# interconnect-board.net
KiCad netlist of a schematic drawn in EAGLE
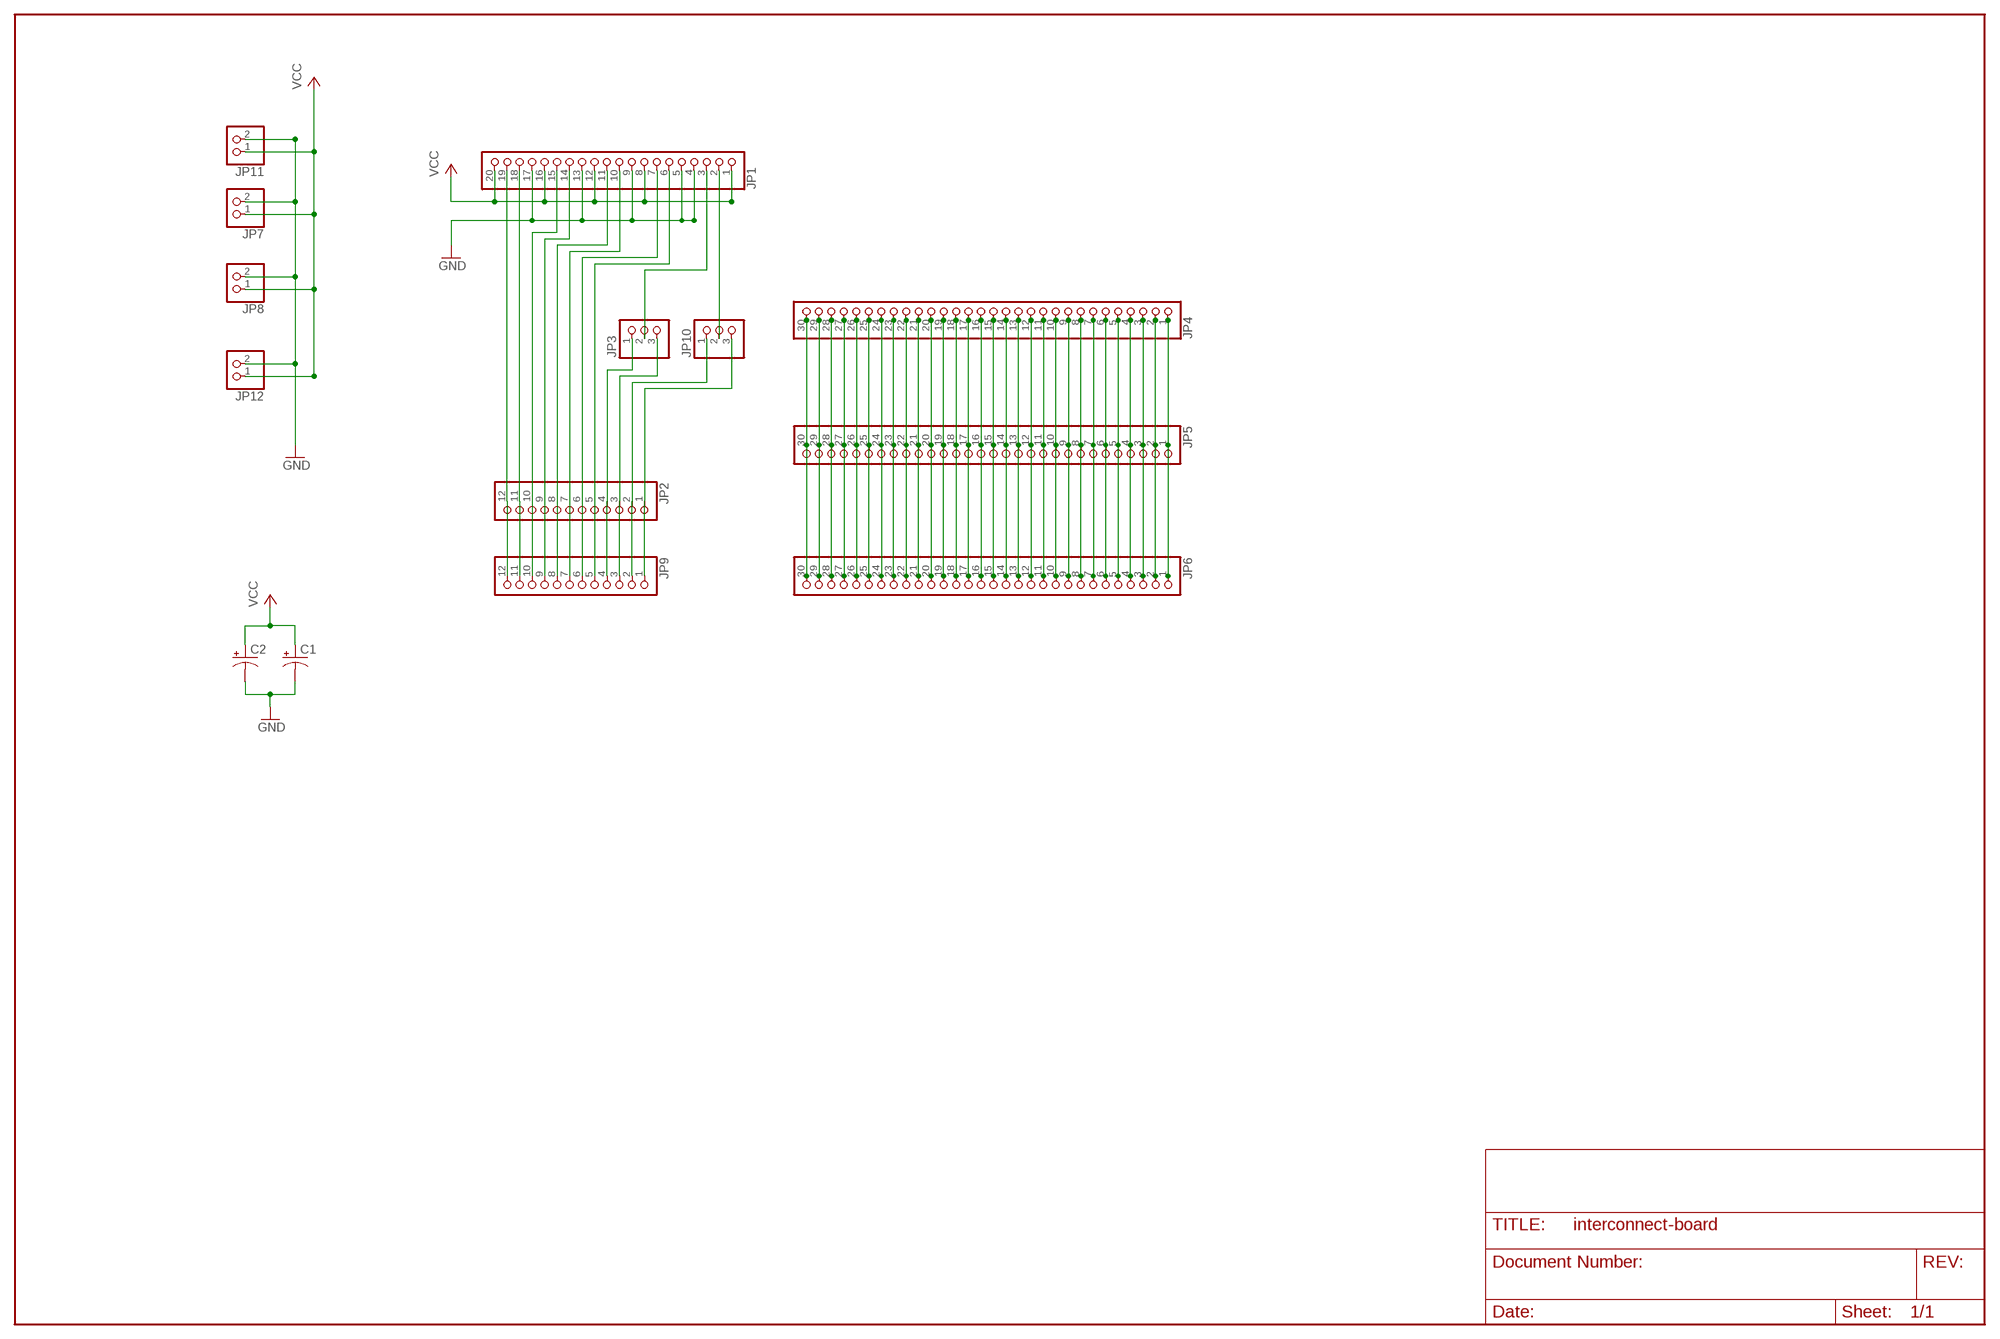
[diagram p0: schematic, sheet 1]

(export (version "E")
  (design (tool "Eeschema 10.0.6"))
  (components
    (comp (ref "C1")
      (value "CPOL-USE15-6AXIAL")
      (footprint "eagle-import:E15-6")
      (libsource (lib "eagle-import") (part "CPOL-USE15-6AXIAL"))
    )
    (comp (ref "C2")
      (value "CPOL-USE15-6AXIAL")
      (footprint "eagle-import:E15-6")
      (libsource (lib "eagle-import") (part "CPOL-USE15-6AXIAL"))
    )
    (comp (ref "JP1")
      (value "PINHD-1X20")
      (footprint "eagle-import:1X20")
      (libsource (lib "eagle-import") (part "PINHD-1X20"))
    )
    (comp (ref "JP2")
      (value "PINHD-1X12")
      (footprint "eagle-import:1X12")
      (libsource (lib "eagle-import") (part "PINHD-1X12"))
    )
    (comp (ref "JP3")
      (value "PINHD-1X3")
      (footprint "eagle-import:1X03")
      (libsource (lib "eagle-import") (part "PINHD-1X3"))
    )
    (comp (ref "JP4")
      (value "PINHD-1X30")
      (footprint "eagle-import:1X30")
      (libsource (lib "eagle-import") (part "PINHD-1X30"))
    )
    (comp (ref "JP5")
      (value "PINHD-1X30")
      (footprint "eagle-import:1X30")
      (libsource (lib "eagle-import") (part "PINHD-1X30"))
    )
    (comp (ref "JP6")
      (value "PINHD-1X30")
      (footprint "eagle-import:1X30")
      (libsource (lib "eagle-import") (part "PINHD-1X30"))
    )
    (comp (ref "JP7")
      (value "PINHD-1X2")
      (footprint "eagle-import:1X02")
      (libsource (lib "eagle-import") (part "PINHD-1X2"))
    )
    (comp (ref "JP8")
      (value "PINHD-1X2")
      (footprint "eagle-import:1X02")
      (libsource (lib "eagle-import") (part "PINHD-1X2"))
    )
    (comp (ref "JP9")
      (value "PINHD-1X12")
      (footprint "eagle-import:1X12")
      (libsource (lib "eagle-import") (part "PINHD-1X12"))
    )
    (comp (ref "JP10")
      (value "PINHD-1X3")
      (footprint "eagle-import:1X03")
      (libsource (lib "eagle-import") (part "PINHD-1X3"))
    )
    (comp (ref "JP11")
      (value "PINHD-1X2")
      (footprint "eagle-import:1X02")
      (libsource (lib "eagle-import") (part "PINHD-1X2"))
    )
    (comp (ref "JP12")
      (value "PINHD-1X2")
      (footprint "eagle-import:1X02")
      (libsource (lib "eagle-import") (part "PINHD-1X2"))
    )
  )
  (nets
    (net (code "1") (name "GND") (class "Default")
      (node (ref "C1") (pin "-") (pinfunction "-_-") (pintype "passive"))
      (node (ref "C2") (pin "-") (pinfunction "-_-") (pintype "passive"))
      (node (ref "JP1") (pin "13") (pinfunction "13_13") (pintype "passive"))
      (node (ref "JP1") (pin "17") (pinfunction "17_17") (pintype "passive"))
      (node (ref "JP1") (pin "4") (pinfunction "4_4") (pintype "passive"))
      (node (ref "JP1") (pin "5") (pinfunction "5_5") (pintype "passive"))
      (node (ref "JP1") (pin "9") (pinfunction "9_9") (pintype "passive"))
      (node (ref "JP11") (pin "2") (pinfunction "2_2") (pintype "passive"))
      (node (ref "JP12") (pin "2") (pinfunction "2_2") (pintype "passive"))
      (node (ref "JP7") (pin "2") (pinfunction "2_2") (pintype "passive"))
      (node (ref "JP8") (pin "2") (pinfunction "2_2") (pintype "passive"))
    )
    (net (code "2") (name "Net-(JP1-Pad2)") (class "Default")
      (node (ref "JP1") (pin "2") (pinfunction "2_2") (pintype "passive"))
      (node (ref "JP10") (pin "2") (pinfunction "2_2") (pintype "passive"))
    )
    (net (code "3") (name "Net-(JP1-Pad3)") (class "Default")
      (node (ref "JP1") (pin "3") (pinfunction "3_3") (pintype "passive"))
      (node (ref "JP3") (pin "2") (pinfunction "2_2") (pintype "passive"))
    )
    (net (code "4") (name "Net-(JP1-Pad6)") (class "Default")
      (node (ref "JP1") (pin "6") (pinfunction "6_6") (pintype "passive"))
      (node (ref "JP2") (pin "5") (pinfunction "5_5") (pintype "passive"))
      (node (ref "JP9") (pin "5") (pinfunction "5_5") (pintype "passive"))
    )
    (net (code "5") (name "Net-(JP1-Pad7)") (class "Default")
      (node (ref "JP1") (pin "7") (pinfunction "7_7") (pintype "passive"))
      (node (ref "JP2") (pin "6") (pinfunction "6_6") (pintype "passive"))
      (node (ref "JP9") (pin "6") (pinfunction "6_6") (pintype "passive"))
    )
    (net (code "6") (name "Net-(JP1-Pad10)") (class "Default")
      (node (ref "JP1") (pin "10") (pinfunction "10_10") (pintype "passive"))
      (node (ref "JP2") (pin "7") (pinfunction "7_7") (pintype "passive"))
      (node (ref "JP9") (pin "7") (pinfunction "7_7") (pintype "passive"))
    )
    (net (code "7") (name "Net-(JP1-Pad11)") (class "Default")
      (node (ref "JP1") (pin "11") (pinfunction "11_11") (pintype "passive"))
      (node (ref "JP2") (pin "8") (pinfunction "8_8") (pintype "passive"))
      (node (ref "JP9") (pin "8") (pinfunction "8_8") (pintype "passive"))
    )
    (net (code "8") (name "Net-(JP1-Pad14)") (class "Default")
      (node (ref "JP1") (pin "14") (pinfunction "14_14") (pintype "passive"))
      (node (ref "JP2") (pin "9") (pinfunction "9_9") (pintype "passive"))
      (node (ref "JP9") (pin "9") (pinfunction "9_9") (pintype "passive"))
    )
    (net (code "9") (name "Net-(JP1-Pad15)") (class "Default")
      (node (ref "JP1") (pin "15") (pinfunction "15_15") (pintype "passive"))
      (node (ref "JP2") (pin "10") (pinfunction "10_10") (pintype "passive"))
      (node (ref "JP9") (pin "10") (pinfunction "10_10") (pintype "passive"))
    )
    (net (code "10") (name "Net-(JP1-Pad18)") (class "Default")
      (node (ref "JP1") (pin "18") (pinfunction "18_18") (pintype "passive"))
      (node (ref "JP2") (pin "11") (pinfunction "11_11") (pintype "passive"))
      (node (ref "JP9") (pin "11") (pinfunction "11_11") (pintype "passive"))
    )
    (net (code "11") (name "Net-(JP1-Pad19)") (class "Default")
      (node (ref "JP1") (pin "19") (pinfunction "19_19") (pintype "passive"))
      (node (ref "JP2") (pin "12") (pinfunction "12_12") (pintype "passive"))
      (node (ref "JP9") (pin "12") (pinfunction "12_12") (pintype "passive"))
    )
    (net (code "12") (name "Net-(JP2-Pad3)") (class "Default")
      (node (ref "JP2") (pin "3") (pinfunction "3_3") (pintype "passive"))
      (node (ref "JP3") (pin "3") (pinfunction "3_3") (pintype "passive"))
      (node (ref "JP9") (pin "3") (pinfunction "3_3") (pintype "passive"))
    )
    (net (code "13") (name "Net-(JP2-Pad4)") (class "Default")
      (node (ref "JP2") (pin "4") (pinfunction "4_4") (pintype "passive"))
      (node (ref "JP3") (pin "1") (pinfunction "1_1") (pintype "passive"))
      (node (ref "JP9") (pin "4") (pinfunction "4_4") (pintype "passive"))
    )
    (net (code "14") (name "Net-(JP4-Pad1)") (class "Default")
      (node (ref "JP4") (pin "1") (pinfunction "1_1") (pintype "passive"))
      (node (ref "JP5") (pin "1") (pinfunction "1_1") (pintype "passive"))
      (node (ref "JP6") (pin "1") (pinfunction "1_1") (pintype "passive"))
    )
    (net (code "15") (name "Net-(JP4-Pad2)") (class "Default")
      (node (ref "JP4") (pin "2") (pinfunction "2_2") (pintype "passive"))
      (node (ref "JP5") (pin "2") (pinfunction "2_2") (pintype "passive"))
      (node (ref "JP6") (pin "2") (pinfunction "2_2") (pintype "passive"))
    )
    (net (code "16") (name "Net-(JP4-Pad3)") (class "Default")
      (node (ref "JP4") (pin "3") (pinfunction "3_3") (pintype "passive"))
      (node (ref "JP5") (pin "3") (pinfunction "3_3") (pintype "passive"))
      (node (ref "JP6") (pin "3") (pinfunction "3_3") (pintype "passive"))
    )
    (net (code "17") (name "Net-(JP4-Pad4)") (class "Default")
      (node (ref "JP4") (pin "4") (pinfunction "4_4") (pintype "passive"))
      (node (ref "JP5") (pin "4") (pinfunction "4_4") (pintype "passive"))
      (node (ref "JP6") (pin "4") (pinfunction "4_4") (pintype "passive"))
    )
    (net (code "18") (name "Net-(JP4-Pad5)") (class "Default")
      (node (ref "JP4") (pin "5") (pinfunction "5_5") (pintype "passive"))
      (node (ref "JP5") (pin "5") (pinfunction "5_5") (pintype "passive"))
      (node (ref "JP6") (pin "5") (pinfunction "5_5") (pintype "passive"))
    )
    (net (code "19") (name "Net-(JP4-Pad6)") (class "Default")
      (node (ref "JP4") (pin "6") (pinfunction "6_6") (pintype "passive"))
      (node (ref "JP5") (pin "6") (pinfunction "6_6") (pintype "passive"))
      (node (ref "JP6") (pin "6") (pinfunction "6_6") (pintype "passive"))
    )
    (net (code "20") (name "Net-(JP4-Pad7)") (class "Default")
      (node (ref "JP4") (pin "7") (pinfunction "7_7") (pintype "passive"))
      (node (ref "JP5") (pin "7") (pinfunction "7_7") (pintype "passive"))
      (node (ref "JP6") (pin "7") (pinfunction "7_7") (pintype "passive"))
    )
    (net (code "21") (name "Net-(JP4-Pad8)") (class "Default")
      (node (ref "JP4") (pin "8") (pinfunction "8_8") (pintype "passive"))
      (node (ref "JP5") (pin "8") (pinfunction "8_8") (pintype "passive"))
      (node (ref "JP6") (pin "8") (pinfunction "8_8") (pintype "passive"))
    )
    (net (code "22") (name "Net-(JP4-Pad9)") (class "Default")
      (node (ref "JP4") (pin "9") (pinfunction "9_9") (pintype "passive"))
      (node (ref "JP5") (pin "9") (pinfunction "9_9") (pintype "passive"))
      (node (ref "JP6") (pin "9") (pinfunction "9_9") (pintype "passive"))
    )
    (net (code "23") (name "Net-(JP4-Pad10)") (class "Default")
      (node (ref "JP4") (pin "10") (pinfunction "10_10") (pintype "passive"))
      (node (ref "JP5") (pin "10") (pinfunction "10_10") (pintype "passive"))
      (node (ref "JP6") (pin "10") (pinfunction "10_10") (pintype "passive"))
    )
    (net (code "24") (name "Net-(JP4-Pad11)") (class "Default")
      (node (ref "JP4") (pin "11") (pinfunction "11_11") (pintype "passive"))
      (node (ref "JP5") (pin "11") (pinfunction "11_11") (pintype "passive"))
      (node (ref "JP6") (pin "11") (pinfunction "11_11") (pintype "passive"))
    )
    (net (code "25") (name "Net-(JP4-Pad12)") (class "Default")
      (node (ref "JP4") (pin "12") (pinfunction "12_12") (pintype "passive"))
      (node (ref "JP5") (pin "12") (pinfunction "12_12") (pintype "passive"))
      (node (ref "JP6") (pin "12") (pinfunction "12_12") (pintype "passive"))
    )
    (net (code "26") (name "Net-(JP4-Pad13)") (class "Default")
      (node (ref "JP4") (pin "13") (pinfunction "13_13") (pintype "passive"))
      (node (ref "JP5") (pin "13") (pinfunction "13_13") (pintype "passive"))
      (node (ref "JP6") (pin "13") (pinfunction "13_13") (pintype "passive"))
    )
    (net (code "27") (name "Net-(JP4-Pad14)") (class "Default")
      (node (ref "JP4") (pin "14") (pinfunction "14_14") (pintype "passive"))
      (node (ref "JP5") (pin "14") (pinfunction "14_14") (pintype "passive"))
      (node (ref "JP6") (pin "14") (pinfunction "14_14") (pintype "passive"))
    )
    (net (code "28") (name "Net-(JP4-Pad15)") (class "Default")
      (node (ref "JP4") (pin "15") (pinfunction "15_15") (pintype "passive"))
      (node (ref "JP5") (pin "15") (pinfunction "15_15") (pintype "passive"))
      (node (ref "JP6") (pin "15") (pinfunction "15_15") (pintype "passive"))
    )
    (net (code "29") (name "Net-(JP4-Pad16)") (class "Default")
      (node (ref "JP4") (pin "16") (pinfunction "16_16") (pintype "passive"))
      (node (ref "JP5") (pin "16") (pinfunction "16_16") (pintype "passive"))
      (node (ref "JP6") (pin "16") (pinfunction "16_16") (pintype "passive"))
    )
    (net (code "30") (name "Net-(JP4-Pad17)") (class "Default")
      (node (ref "JP4") (pin "17") (pinfunction "17_17") (pintype "passive"))
      (node (ref "JP5") (pin "17") (pinfunction "17_17") (pintype "passive"))
      (node (ref "JP6") (pin "17") (pinfunction "17_17") (pintype "passive"))
    )
    (net (code "31") (name "Net-(JP4-Pad18)") (class "Default")
      (node (ref "JP4") (pin "18") (pinfunction "18_18") (pintype "passive"))
      (node (ref "JP5") (pin "18") (pinfunction "18_18") (pintype "passive"))
      (node (ref "JP6") (pin "18") (pinfunction "18_18") (pintype "passive"))
    )
    (net (code "32") (name "Net-(JP4-Pad19)") (class "Default")
      (node (ref "JP4") (pin "19") (pinfunction "19_19") (pintype "passive"))
      (node (ref "JP5") (pin "19") (pinfunction "19_19") (pintype "passive"))
      (node (ref "JP6") (pin "19") (pinfunction "19_19") (pintype "passive"))
    )
    (net (code "33") (name "Net-(JP4-Pad20)") (class "Default")
      (node (ref "JP4") (pin "20") (pinfunction "20_20") (pintype "passive"))
      (node (ref "JP5") (pin "20") (pinfunction "20_20") (pintype "passive"))
      (node (ref "JP6") (pin "20") (pinfunction "20_20") (pintype "passive"))
    )
    (net (code "34") (name "Net-(JP4-Pad21)") (class "Default")
      (node (ref "JP4") (pin "21") (pinfunction "21_21") (pintype "passive"))
      (node (ref "JP5") (pin "21") (pinfunction "21_21") (pintype "passive"))
      (node (ref "JP6") (pin "21") (pinfunction "21_21") (pintype "passive"))
    )
    (net (code "35") (name "Net-(JP4-Pad22)") (class "Default")
      (node (ref "JP4") (pin "22") (pinfunction "22_22") (pintype "passive"))
      (node (ref "JP5") (pin "22") (pinfunction "22_22") (pintype "passive"))
      (node (ref "JP6") (pin "22") (pinfunction "22_22") (pintype "passive"))
    )
    (net (code "36") (name "Net-(JP4-Pad23)") (class "Default")
      (node (ref "JP4") (pin "23") (pinfunction "23_23") (pintype "passive"))
      (node (ref "JP5") (pin "23") (pinfunction "23_23") (pintype "passive"))
      (node (ref "JP6") (pin "23") (pinfunction "23_23") (pintype "passive"))
    )
    (net (code "37") (name "Net-(JP4-Pad24)") (class "Default")
      (node (ref "JP4") (pin "24") (pinfunction "24_24") (pintype "passive"))
      (node (ref "JP5") (pin "24") (pinfunction "24_24") (pintype "passive"))
      (node (ref "JP6") (pin "24") (pinfunction "24_24") (pintype "passive"))
    )
    (net (code "38") (name "Net-(JP4-Pad25)") (class "Default")
      (node (ref "JP4") (pin "25") (pinfunction "25_25") (pintype "passive"))
      (node (ref "JP5") (pin "25") (pinfunction "25_25") (pintype "passive"))
      (node (ref "JP6") (pin "25") (pinfunction "25_25") (pintype "passive"))
    )
    (net (code "39") (name "Net-(JP4-Pad26)") (class "Default")
      (node (ref "JP4") (pin "26") (pinfunction "26_26") (pintype "passive"))
      (node (ref "JP5") (pin "26") (pinfunction "26_26") (pintype "passive"))
      (node (ref "JP6") (pin "26") (pinfunction "26_26") (pintype "passive"))
    )
    (net (code "40") (name "Net-(JP4-Pad27)") (class "Default")
      (node (ref "JP4") (pin "27") (pinfunction "27_27") (pintype "passive"))
      (node (ref "JP5") (pin "27") (pinfunction "27_27") (pintype "passive"))
      (node (ref "JP6") (pin "27") (pinfunction "27_27") (pintype "passive"))
    )
    (net (code "41") (name "Net-(JP4-Pad28)") (class "Default")
      (node (ref "JP4") (pin "28") (pinfunction "28_28") (pintype "passive"))
      (node (ref "JP5") (pin "28") (pinfunction "28_28") (pintype "passive"))
      (node (ref "JP6") (pin "28") (pinfunction "28_28") (pintype "passive"))
    )
    (net (code "42") (name "Net-(JP4-Pad29)") (class "Default")
      (node (ref "JP4") (pin "29") (pinfunction "29_29") (pintype "passive"))
      (node (ref "JP5") (pin "29") (pinfunction "29_29") (pintype "passive"))
      (node (ref "JP6") (pin "29") (pinfunction "29_29") (pintype "passive"))
    )
    (net (code "43") (name "Net-(JP4-Pad30)") (class "Default")
      (node (ref "JP4") (pin "30") (pinfunction "30_30") (pintype "passive"))
      (node (ref "JP5") (pin "30") (pinfunction "30_30") (pintype "passive"))
      (node (ref "JP6") (pin "30") (pinfunction "30_30") (pintype "passive"))
    )
    (net (code "44") (name "Net-(JP10-Pad1)") (class "Default")
      (node (ref "JP10") (pin "1") (pinfunction "1_1") (pintype "passive"))
      (node (ref "JP2") (pin "2") (pinfunction "2_2") (pintype "passive"))
      (node (ref "JP9") (pin "2") (pinfunction "2_2") (pintype "passive"))
    )
    (net (code "45") (name "Net-(JP10-Pad3)") (class "Default")
      (node (ref "JP10") (pin "3") (pinfunction "3_3") (pintype "passive"))
      (node (ref "JP2") (pin "1") (pinfunction "1_1") (pintype "passive"))
      (node (ref "JP9") (pin "1") (pinfunction "1_1") (pintype "passive"))
    )
    (net (code "46") (name "VCC") (class "Default")
      (node (ref "C1") (pin "+") (pinfunction "+_+") (pintype "passive"))
      (node (ref "C2") (pin "+") (pinfunction "+_+") (pintype "passive"))
      (node (ref "JP1") (pin "1") (pinfunction "1_1") (pintype "passive"))
      (node (ref "JP1") (pin "12") (pinfunction "12_12") (pintype "passive"))
      (node (ref "JP1") (pin "16") (pinfunction "16_16") (pintype "passive"))
      (node (ref "JP1") (pin "20") (pinfunction "20_20") (pintype "passive"))
      (node (ref "JP1") (pin "8") (pinfunction "8_8") (pintype "passive"))
      (node (ref "JP11") (pin "1") (pinfunction "1_1") (pintype "passive"))
      (node (ref "JP12") (pin "1") (pinfunction "1_1") (pintype "passive"))
      (node (ref "JP7") (pin "1") (pinfunction "1_1") (pintype "passive"))
      (node (ref "JP8") (pin "1") (pinfunction "1_1") (pintype "passive"))
    )
  )
)
